# 16_-ETH_SWITCH.net
KiCad netlist of a schematic drawn in Altium Designer
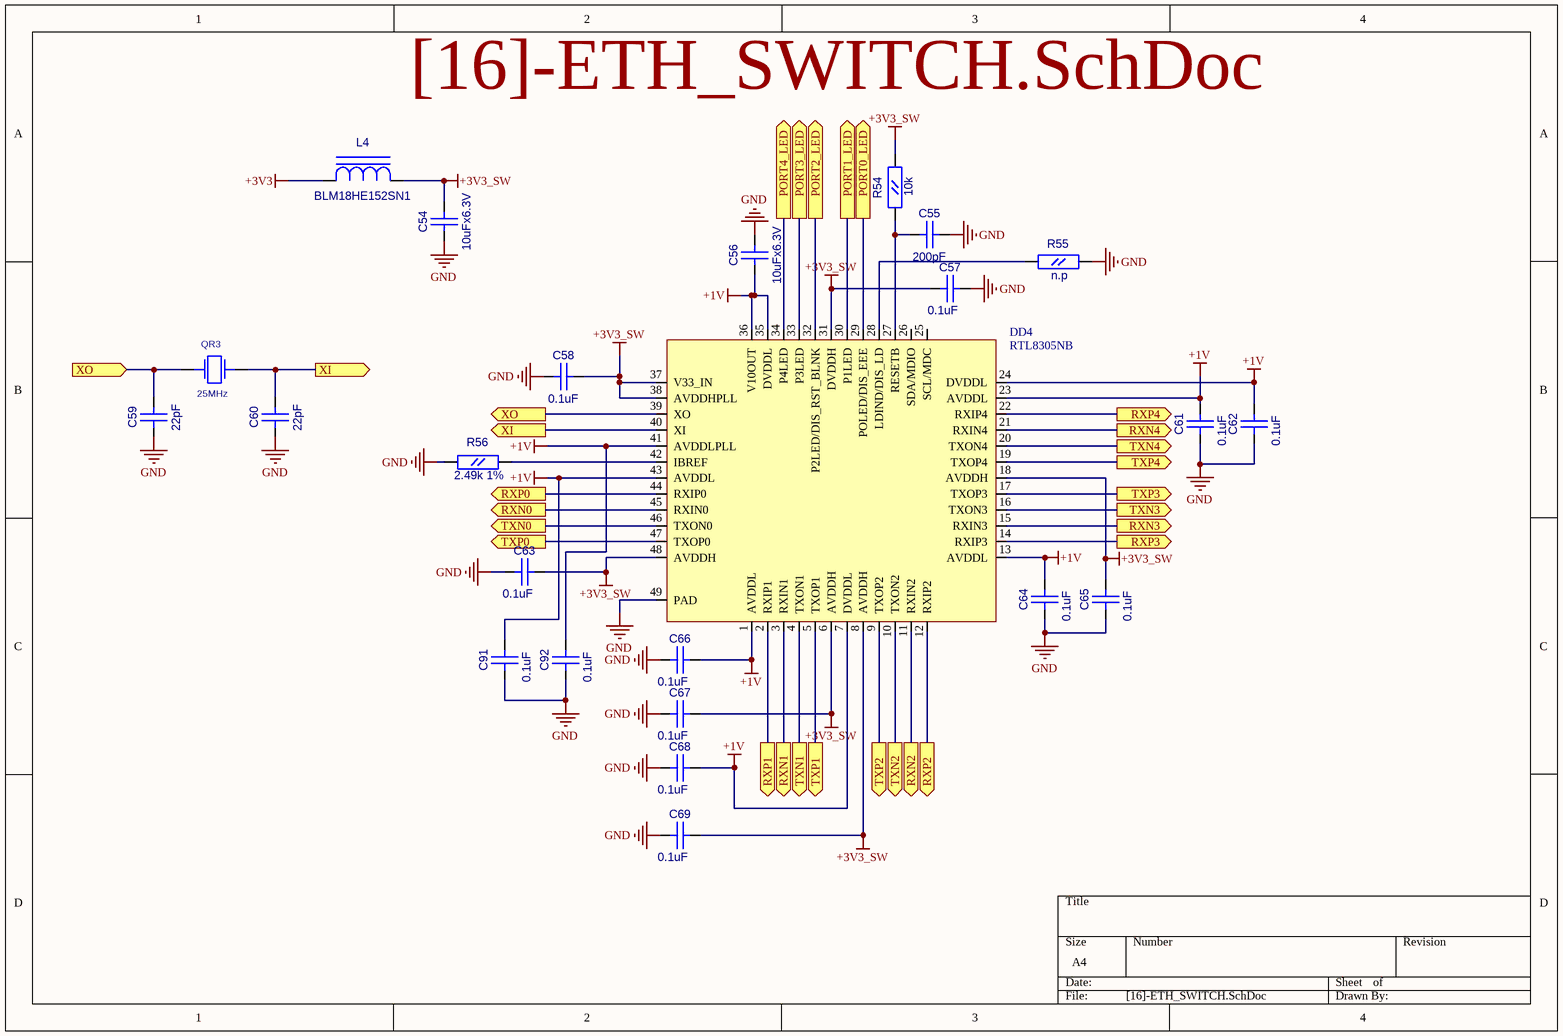
[diagram p0: [16]-ETH_SWITCH.SchDoc]

(export (version "E")
  (design (tool "Eeschema 10.0.6"))
  (components
    (comp (ref "C54")
      (value "10uFx6.3V")
      (footprint "CC0805")
      (description "CC0805")
      (libsource (lib "fizik_lib") (part "CC0805"))
    )
    (comp (ref "C55")
      (value "200pF")
      (footprint "CC0603")
      (description "CC0603")
      (libsource (lib "fizik_lib") (part "CC0603"))
    )
    (comp (ref "C56")
      (value "10uFx6.3V")
      (footprint "CC0805")
      (description "CC0805")
      (libsource (lib "fizik_lib") (part "CC0805"))
    )
    (comp (ref "C57")
      (value "0.1uF")
      (footprint "CC0603")
      (description "CC0603")
      (libsource (lib "fizik_lib") (part "CC0603"))
    )
    (comp (ref "C58")
      (value "0.1uF")
      (footprint "CC0603")
      (description "CC0603")
      (libsource (lib "fizik_lib") (part "CC0603"))
    )
    (comp (ref "C59")
      (value "22pF")
      (footprint "CC0603")
      (description "CC0603")
      (libsource (lib "fizik_lib") (part "CC0603"))
    )
    (comp (ref "C60")
      (value "22pF")
      (footprint "CC0603")
      (description "CC0603")
      (libsource (lib "fizik_lib") (part "CC0603"))
    )
    (comp (ref "C61")
      (value "0.1uF")
      (footprint "CC0603")
      (description "CC0603")
      (libsource (lib "fizik_lib") (part "CC0603"))
    )
    (comp (ref "C62")
      (value "0.1uF")
      (footprint "CC0603")
      (description "CC0603")
      (libsource (lib "fizik_lib") (part "CC0603"))
    )
    (comp (ref "C63")
      (value "0.1uF")
      (footprint "CC0603")
      (description "CC0603")
      (libsource (lib "fizik_lib") (part "CC0603"))
    )
    (comp (ref "C64")
      (value "0.1uF")
      (footprint "CC0603")
      (description "CC0603")
      (libsource (lib "fizik_lib") (part "CC0603"))
    )
    (comp (ref "C65")
      (value "0.1uF")
      (footprint "CC0603")
      (description "CC0603")
      (libsource (lib "fizik_lib") (part "CC0603"))
    )
    (comp (ref "C66")
      (value "0.1uF")
      (footprint "CC0603")
      (description "CC0603")
      (libsource (lib "fizik_lib") (part "CC0603"))
    )
    (comp (ref "C67")
      (value "0.1uF")
      (footprint "CC0603")
      (description "CC0603")
      (libsource (lib "fizik_lib") (part "CC0603"))
    )
    (comp (ref "C68")
      (value "0.1uF")
      (footprint "CC0603")
      (description "CC0603")
      (libsource (lib "fizik_lib") (part "CC0603"))
    )
    (comp (ref "C69")
      (value "0.1uF")
      (footprint "CC0603")
      (description "CC0603")
      (libsource (lib "fizik_lib") (part "CC0603"))
    )
    (comp (ref "C91")
      (value "0.1uF")
      (footprint "CC0603")
      (description "CC0603")
      (libsource (lib "fizik_lib") (part "CC0603"))
    )
    (comp (ref "C92")
      (value "0.1uF")
      (footprint "CC0603")
      (description "CC0603")
      (libsource (lib "fizik_lib") (part "CC0603"))
    )
    (comp (ref "DD4")
      (value "RTL8305NB")
      (footprint "QFN48_ISL")
      (libsource (lib "fizik_lib") (part "RTL8305NB"))
    )
    (comp (ref "L4")
      (value "BLM18HE152SN1")
      (footprint "L0603")
      (description "L0603")
      (libsource (lib "gprs_modem_2") (part "L0603"))
    )
    (comp (ref "QR3")
      (value "25MHz")
      (footprint "AC5032_2")
      (description "AC5032/2")
      (libsource (lib "fizik_lib") (part "AC5032_2"))
    )
    (comp (ref "R54")
      (value "10k")
      (footprint "RC0603")
      (description "RC0603")
      (libsource (lib "fizik_lib") (part "RC0603"))
    )
    (comp (ref "R55")
      (value "n.p")
      (footprint "RC0603")
      (description "RC0603")
      (libsource (lib "fizik_lib") (part "RC0603"))
    )
    (comp (ref "R56")
      (value "2.49k 1%")
      (footprint "RC0603")
      (description "RC0603")
      (libsource (lib "fizik_lib") (part "RC0603"))
    )
  )
  (nets
    (net (code "1") (name "+1V") (class "Default")
      (node (ref "C56") (pin "1") (pinfunction "A_1") (pintype "passive"))
      (node (ref "C61") (pin "2") (pinfunction "B_2") (pintype "passive"))
      (node (ref "C62") (pin "2") (pinfunction "B_2") (pintype "passive"))
      (node (ref "C64") (pin "2") (pinfunction "B_2") (pintype "passive"))
      (node (ref "C66") (pin "2") (pinfunction "B_2") (pintype "passive"))
      (node (ref "C68") (pin "2") (pinfunction "B_2") (pintype "passive"))
      (node (ref "C91") (pin "2") (pinfunction "B_2") (pintype "passive"))
      (node (ref "C92") (pin "2") (pinfunction "B_2") (pintype "passive"))
      (node (ref "DD4") (pin "1") (pinfunction "AVDDL_1") (pintype "passive"))
      (node (ref "DD4") (pin "13") (pinfunction "AVDDL_13") (pintype "passive"))
      (node (ref "DD4") (pin "23") (pinfunction "AVDDL_23") (pintype "passive"))
      (node (ref "DD4") (pin "24") (pinfunction "DVDDL_24") (pintype "passive"))
      (node (ref "DD4") (pin "35") (pinfunction "DVDDL_35") (pintype "passive"))
      (node (ref "DD4") (pin "36") (pinfunction "V10OUT_36") (pintype "passive"))
      (node (ref "DD4") (pin "41") (pinfunction "AVDDLPLL_41") (pintype "passive"))
      (node (ref "DD4") (pin "43") (pinfunction "AVDDL_43") (pintype "passive"))
      (node (ref "DD4") (pin "7") (pinfunction "DVDDL_7") (pintype "passive"))
    )
    (net (code "2") (name "+3V3") (class "Default")
      (node (ref "L4") (pin "1") (pinfunction "A_1") (pintype "passive"))
    )
    (net (code "3") (name "+3V3_SW") (class "Default")
      (node (ref "C54") (pin "2") (pinfunction "B_2") (pintype "passive"))
      (node (ref "C57") (pin "1") (pinfunction "A_1") (pintype "passive"))
      (node (ref "C58") (pin "2") (pinfunction "B_2") (pintype "passive"))
      (node (ref "C63") (pin "2") (pinfunction "B_2") (pintype "passive"))
      (node (ref "C65") (pin "2") (pinfunction "B_2") (pintype "passive"))
      (node (ref "C67") (pin "2") (pinfunction "B_2") (pintype "passive"))
      (node (ref "C69") (pin "2") (pinfunction "B_2") (pintype "passive"))
      (node (ref "DD4") (pin "18") (pinfunction "AVDDH_18") (pintype "passive"))
      (node (ref "DD4") (pin "31") (pinfunction "DVDDH_31") (pintype "passive"))
      (node (ref "DD4") (pin "37") (pinfunction "V33_IN_37") (pintype "passive"))
      (node (ref "DD4") (pin "38") (pinfunction "AVDDHPLL_38") (pintype "passive"))
      (node (ref "DD4") (pin "48") (pinfunction "AVDDH_48") (pintype "passive"))
      (node (ref "DD4") (pin "6") (pinfunction "AVDDH_6") (pintype "passive"))
      (node (ref "DD4") (pin "8") (pinfunction "AVDDH_8") (pintype "passive"))
      (node (ref "L4") (pin "2") (pinfunction "C_2") (pintype "passive"))
      (node (ref "R54") (pin "2") (pinfunction "B_2") (pintype "passive"))
    )
    (net (code "4") (name "/PORT0_LED") (class "Default")
      (node (ref "DD4") (pin "29") (pinfunction "POLED/DIS_EEE_29") (pintype "passive"))
    )
    (net (code "5") (name "/PORT1_LED") (class "Default")
      (node (ref "DD4") (pin "30") (pinfunction "P1LED_30") (pintype "passive"))
    )
    (net (code "6") (name "/PORT2_LED") (class "Default")
      (node (ref "DD4") (pin "32") (pinfunction "P2LED/DIS_RST_BLNK_32") (pintype "passive"))
    )
    (net (code "7") (name "/PORT3_LED") (class "Default")
      (node (ref "DD4") (pin "33") (pinfunction "P3LED_33") (pintype "passive"))
    )
    (net (code "8") (name "/PORT4_LED") (class "Default")
      (node (ref "DD4") (pin "34") (pinfunction "P4LED_34") (pintype "passive"))
    )
    (net (code "9") (name "/RXN0") (class "Default")
      (node (ref "DD4") (pin "45") (pinfunction "RXIN0_45") (pintype "passive"))
    )
    (net (code "10") (name "/RXN1") (class "Default")
      (node (ref "DD4") (pin "3") (pinfunction "RXIN1_3") (pintype "passive"))
    )
    (net (code "11") (name "/RXN2") (class "Default")
      (node (ref "DD4") (pin "11") (pinfunction "RXIN2_11") (pintype "passive"))
    )
    (net (code "12") (name "/RXN3") (class "Default")
      (node (ref "DD4") (pin "15") (pinfunction "RXIN3_15") (pintype "passive"))
    )
    (net (code "13") (name "/RXN4") (class "Default")
      (node (ref "DD4") (pin "21") (pinfunction "RXIN4_21") (pintype "passive"))
    )
    (net (code "14") (name "/RXP0") (class "Default")
      (node (ref "DD4") (pin "44") (pinfunction "RXIP0_44") (pintype "passive"))
    )
    (net (code "15") (name "/RXP1") (class "Default")
      (node (ref "DD4") (pin "2") (pinfunction "RXIP1_2") (pintype "passive"))
    )
    (net (code "16") (name "/RXP2") (class "Default")
      (node (ref "DD4") (pin "12") (pinfunction "RXIP2_12") (pintype "passive"))
    )
    (net (code "17") (name "/RXP3") (class "Default")
      (node (ref "DD4") (pin "14") (pinfunction "RXIP3_14") (pintype "passive"))
    )
    (net (code "18") (name "/RXP4") (class "Default")
      (node (ref "DD4") (pin "22") (pinfunction "RXIP4_22") (pintype "passive"))
    )
    (net (code "19") (name "/TXN0") (class "Default")
      (node (ref "DD4") (pin "46") (pinfunction "TXON0_46") (pintype "passive"))
    )
    (net (code "20") (name "/TXN1") (class "Default")
      (node (ref "DD4") (pin "4") (pinfunction "TXON1_4") (pintype "passive"))
    )
    (net (code "21") (name "/TXN2") (class "Default")
      (node (ref "DD4") (pin "10") (pinfunction "TXON2_10") (pintype "passive"))
    )
    (net (code "22") (name "/TXN3") (class "Default")
      (node (ref "DD4") (pin "16") (pinfunction "TXON3_16") (pintype "passive"))
    )
    (net (code "23") (name "/TXN4") (class "Default")
      (node (ref "DD4") (pin "20") (pinfunction "TXON4_20") (pintype "passive"))
    )
    (net (code "24") (name "/TXP0") (class "Default")
      (node (ref "DD4") (pin "47") (pinfunction "TXOP0_47") (pintype "passive"))
    )
    (net (code "25") (name "/TXP1") (class "Default")
      (node (ref "DD4") (pin "5") (pinfunction "TXOP1_5") (pintype "passive"))
    )
    (net (code "26") (name "/TXP2") (class "Default")
      (node (ref "DD4") (pin "9") (pinfunction "TXOP2_9") (pintype "passive"))
    )
    (net (code "27") (name "/TXP3") (class "Default")
      (node (ref "DD4") (pin "17") (pinfunction "TXOP3_17") (pintype "passive"))
    )
    (net (code "28") (name "/TXP4") (class "Default")
      (node (ref "DD4") (pin "19") (pinfunction "TXOP4_19") (pintype "passive"))
    )
    (net (code "29") (name "/XI") (class "Default")
      (node (ref "C60") (pin "2") (pinfunction "B_2") (pintype "passive"))
      (node (ref "DD4") (pin "40") (pinfunction "XI_40") (pintype "passive"))
      (node (ref "QR3") (pin "2") (pintype "passive"))
    )
    (net (code "30") (name "/XO") (class "Default")
      (node (ref "C59") (pin "2") (pinfunction "B_2") (pintype "passive"))
      (node (ref "DD4") (pin "39") (pinfunction "XO_39") (pintype "passive"))
      (node (ref "QR3") (pin "1") (pintype "passive"))
    )
    (net (code "31") (name "GND") (class "Default")
      (node (ref "C54") (pin "1") (pinfunction "A_1") (pintype "passive"))
      (node (ref "C55") (pin "2") (pinfunction "B_2") (pintype "passive"))
      (node (ref "C56") (pin "2") (pinfunction "B_2") (pintype "passive"))
      (node (ref "C57") (pin "2") (pinfunction "B_2") (pintype "passive"))
      (node (ref "C58") (pin "1") (pinfunction "A_1") (pintype "passive"))
      (node (ref "C59") (pin "1") (pinfunction "A_1") (pintype "passive"))
      (node (ref "C60") (pin "1") (pinfunction "A_1") (pintype "passive"))
      (node (ref "C61") (pin "1") (pinfunction "A_1") (pintype "passive"))
      (node (ref "C62") (pin "1") (pinfunction "A_1") (pintype "passive"))
      (node (ref "C63") (pin "1") (pinfunction "A_1") (pintype "passive"))
      (node (ref "C64") (pin "1") (pinfunction "A_1") (pintype "passive"))
      (node (ref "C65") (pin "1") (pinfunction "A_1") (pintype "passive"))
      (node (ref "C66") (pin "1") (pinfunction "A_1") (pintype "passive"))
      (node (ref "C67") (pin "1") (pinfunction "A_1") (pintype "passive"))
      (node (ref "C68") (pin "1") (pinfunction "A_1") (pintype "passive"))
      (node (ref "C69") (pin "1") (pinfunction "A_1") (pintype "passive"))
      (node (ref "C91") (pin "1") (pinfunction "A_1") (pintype "passive"))
      (node (ref "C92") (pin "1") (pinfunction "A_1") (pintype "passive"))
      (node (ref "DD4") (pin "49") (pinfunction "PAD_49") (pintype "passive"))
      (node (ref "R55") (pin "2") (pinfunction "B_2") (pintype "passive"))
      (node (ref "R56") (pin "1") (pinfunction "A_1") (pintype "passive"))
    )
    (net (code "32") (name "Net-(C55-A)") (class "Default")
      (node (ref "C55") (pin "1") (pinfunction "A_1") (pintype "passive"))
      (node (ref "DD4") (pin "27") (pinfunction "RESETB_27") (pintype "passive"))
      (node (ref "R54") (pin "1") (pinfunction "A_1") (pintype "passive"))
    )
    (net (code "33") (name "Net-(DD4-IBREF)") (class "Default")
      (node (ref "DD4") (pin "42") (pinfunction "IBREF_42") (pintype "passive"))
      (node (ref "R56") (pin "2") (pinfunction "B_2") (pintype "passive"))
    )
    (net (code "34") (name "Net-(DD4-LDIND{slash}DIS_LD)") (class "Default")
      (node (ref "DD4") (pin "28") (pinfunction "LDIND/DIS_LD_28") (pintype "passive"))
      (node (ref "R55") (pin "1") (pinfunction "A_1") (pintype "passive"))
    )
    (net (code "35") (name "unconnected-(DD4-SCL{slash}MDC-Pad25)") (class "Default")
      (node (ref "DD4") (pin "25") (pinfunction "SCL/MDC_25") (pintype "passive"))
    )
    (net (code "36") (name "unconnected-(DD4-SDA{slash}MDIO-Pad26)") (class "Default")
      (node (ref "DD4") (pin "26") (pinfunction "SDA/MDIO_26") (pintype "passive"))
    )
  )
)
